# distance_measurement.net
KiCad netlist of a schematic drawn in Altium Designer
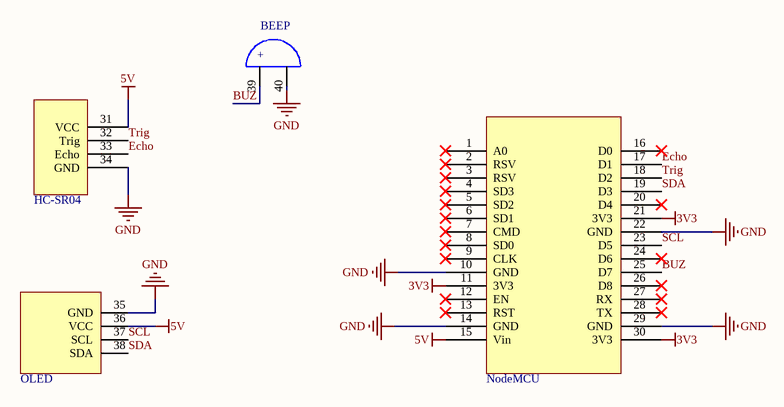
[diagram p0: distance measurement.SchDoc]

(export (version "E")
  (design (tool "Eeschema 10.0.6"))
  (components
    (comp (ref "B")
      (value "BEEP")
      (footprint "BUZ-TH_BD9.0-P5.00-D0.6-FD")
      (libsource (lib "BEEP") (part "BEEP"))
    )
    (comp (ref "H") (value "HC-SR04") (footprint "HC-SR04") (libsource (lib "HC-SR04") (part "HC-SR04")))
    (comp (ref "O") (value "OLED") (footprint "0.96OLEDIIC") (libsource (lib "0.96OLED") (part "OLED")))
    (comp (ref "U")
      (value "NodeMCU")
      (footprint "PCBComponent_1 - duplicate")
      (libsource (lib "NodeMCU") (part "NodeMCU"))
    )
  )
  (nets
    (net (code "1") (name "/BUZ") (class "Default")
      (node (ref "B") (pin "39") (pinfunction "posi_39") (pintype "passive"))
      (node (ref "U") (pin "25") (pinfunction "D7_25") (pintype "passive"))
    )
    (net (code "2") (name "/Echo") (class "Default")
      (node (ref "H") (pin "33") (pinfunction "Echo_33") (pintype "passive"))
      (node (ref "U") (pin "17") (pinfunction "D1_17") (pintype "passive"))
    )
    (net (code "3") (name "/SCL") (class "Default")
      (node (ref "O") (pin "37") (pinfunction "SCL_37") (pintype "passive"))
      (node (ref "U") (pin "23") (pinfunction "D5_23") (pintype "passive"))
    )
    (net (code "4") (name "/SDA") (class "Default")
      (node (ref "O") (pin "38") (pinfunction "SDA_38") (pintype "passive"))
      (node (ref "U") (pin "19") (pinfunction "D3_19") (pintype "passive"))
    )
    (net (code "5") (name "/Trig") (class "Default")
      (node (ref "H") (pin "32") (pinfunction "Trig_32") (pintype "passive"))
      (node (ref "U") (pin "18") (pinfunction "D2_18") (pintype "passive"))
    )
    (net (code "6") (name "3V3") (class "Default")
      (node (ref "U") (pin "11") (pinfunction "3V3_11") (pintype "passive"))
      (node (ref "U") (pin "21") (pinfunction "3V3_21") (pintype "passive"))
      (node (ref "U") (pin "30") (pinfunction "3V3_30") (pintype "passive"))
    )
    (net (code "7") (name "5V") (class "Default")
      (node (ref "H") (pin "31") (pinfunction "VCC_31") (pintype "passive"))
      (node (ref "O") (pin "36") (pinfunction "VCC_36") (pintype "passive"))
      (node (ref "U") (pin "15") (pinfunction "Vin_15") (pintype "passive"))
    )
    (net (code "8") (name "GND") (class "Default")
      (node (ref "B") (pin "40") (pinfunction "nega_40") (pintype "passive"))
      (node (ref "H") (pin "34") (pinfunction "GND_34") (pintype "passive"))
      (node (ref "O") (pin "35") (pinfunction "GND_35") (pintype "passive"))
      (node (ref "U") (pin "10") (pinfunction "GND_10") (pintype "passive"))
      (node (ref "U") (pin "14") (pinfunction "GND_14") (pintype "passive"))
      (node (ref "U") (pin "22") (pinfunction "GND_22") (pintype "passive"))
      (node (ref "U") (pin "29") (pinfunction "GND_29") (pintype "passive"))
    )
    (net (code "9") (name "unconnected-(U-A0-Pad1)") (class "Default")
      (node (ref "U") (pin "1") (pinfunction "A0_1") (pintype "passive+no_connect"))
    )
    (net (code "10") (name "unconnected-(U-CLK-Pad9)") (class "Default")
      (node (ref "U") (pin "9") (pinfunction "CLK_9") (pintype "passive+no_connect"))
    )
    (net (code "11") (name "unconnected-(U-CMD-Pad7)") (class "Default")
      (node (ref "U") (pin "7") (pinfunction "CMD_7") (pintype "passive+no_connect"))
    )
    (net (code "12") (name "unconnected-(U-D0-Pad16)") (class "Default")
      (node (ref "U") (pin "16") (pinfunction "D0_16") (pintype "passive+no_connect"))
    )
    (net (code "13") (name "unconnected-(U-D4-Pad20)") (class "Default")
      (node (ref "U") (pin "20") (pinfunction "D4_20") (pintype "passive+no_connect"))
    )
    (net (code "14") (name "unconnected-(U-D6-Pad24)") (class "Default")
      (node (ref "U") (pin "24") (pinfunction "D6_24") (pintype "passive+no_connect"))
    )
    (net (code "15") (name "unconnected-(U-D8-Pad26)") (class "Default")
      (node (ref "U") (pin "26") (pinfunction "D8_26") (pintype "passive+no_connect"))
    )
    (net (code "16") (name "unconnected-(U-EN-Pad12)") (class "Default")
      (node (ref "U") (pin "12") (pinfunction "EN_12") (pintype "passive+no_connect"))
    )
    (net (code "17") (name "unconnected-(U-RST-Pad13)") (class "Default")
      (node (ref "U") (pin "13") (pinfunction "RST_13") (pintype "passive+no_connect"))
    )
    (net (code "18") (name "unconnected-(U-RSV-Pad2)") (class "Default")
      (node (ref "U") (pin "2") (pinfunction "RSV_2") (pintype "passive+no_connect"))
    )
    (net (code "19") (name "unconnected-(U-RSV-Pad3)") (class "Default")
      (node (ref "U") (pin "3") (pinfunction "RSV_3") (pintype "passive+no_connect"))
    )
    (net (code "20") (name "unconnected-(U-RX-Pad27)") (class "Default")
      (node (ref "U") (pin "27") (pinfunction "RX_27") (pintype "passive+no_connect"))
    )
    (net (code "21") (name "unconnected-(U-SD0-Pad8)") (class "Default")
      (node (ref "U") (pin "8") (pinfunction "SD0_8") (pintype "passive+no_connect"))
    )
    (net (code "22") (name "unconnected-(U-SD1-Pad6)") (class "Default")
      (node (ref "U") (pin "6") (pinfunction "SD1_6") (pintype "passive+no_connect"))
    )
    (net (code "23") (name "unconnected-(U-SD2-Pad5)") (class "Default")
      (node (ref "U") (pin "5") (pinfunction "SD2_5") (pintype "passive+no_connect"))
    )
    (net (code "24") (name "unconnected-(U-SD3-Pad4)") (class "Default")
      (node (ref "U") (pin "4") (pinfunction "SD3_4") (pintype "passive+no_connect"))
    )
    (net (code "25") (name "unconnected-(U-TX-Pad28)") (class "Default")
      (node (ref "U") (pin "28") (pinfunction "TX_28") (pintype "passive+no_connect"))
    )
  )
)
